# Mainboard.net
KiCad netlist of a schematic drawn in Altium Designer
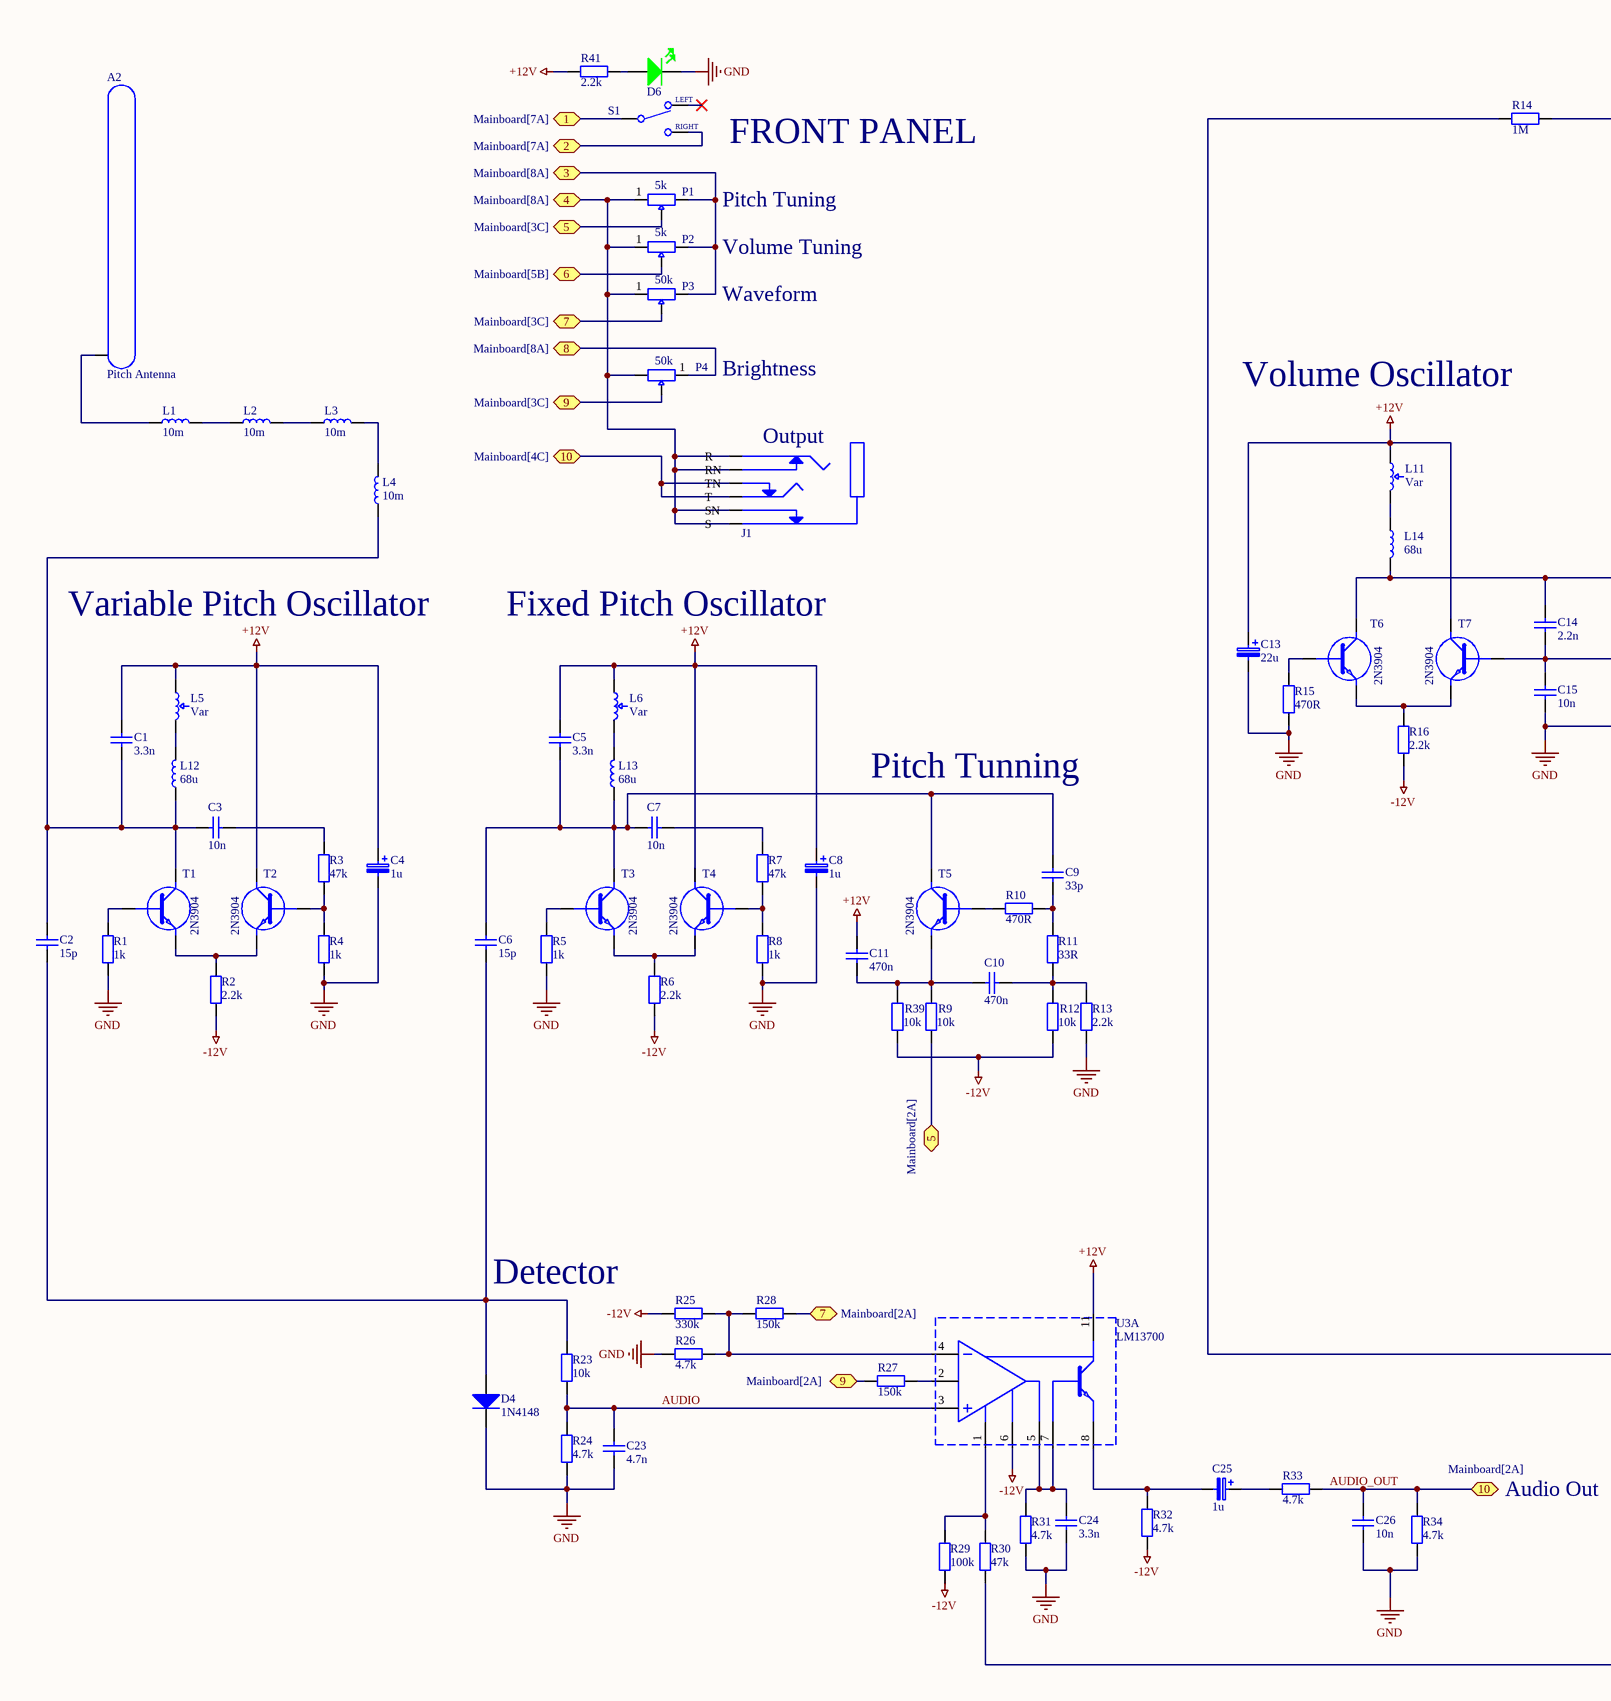
[diagram p0: Mainboard.SchDoc, left]
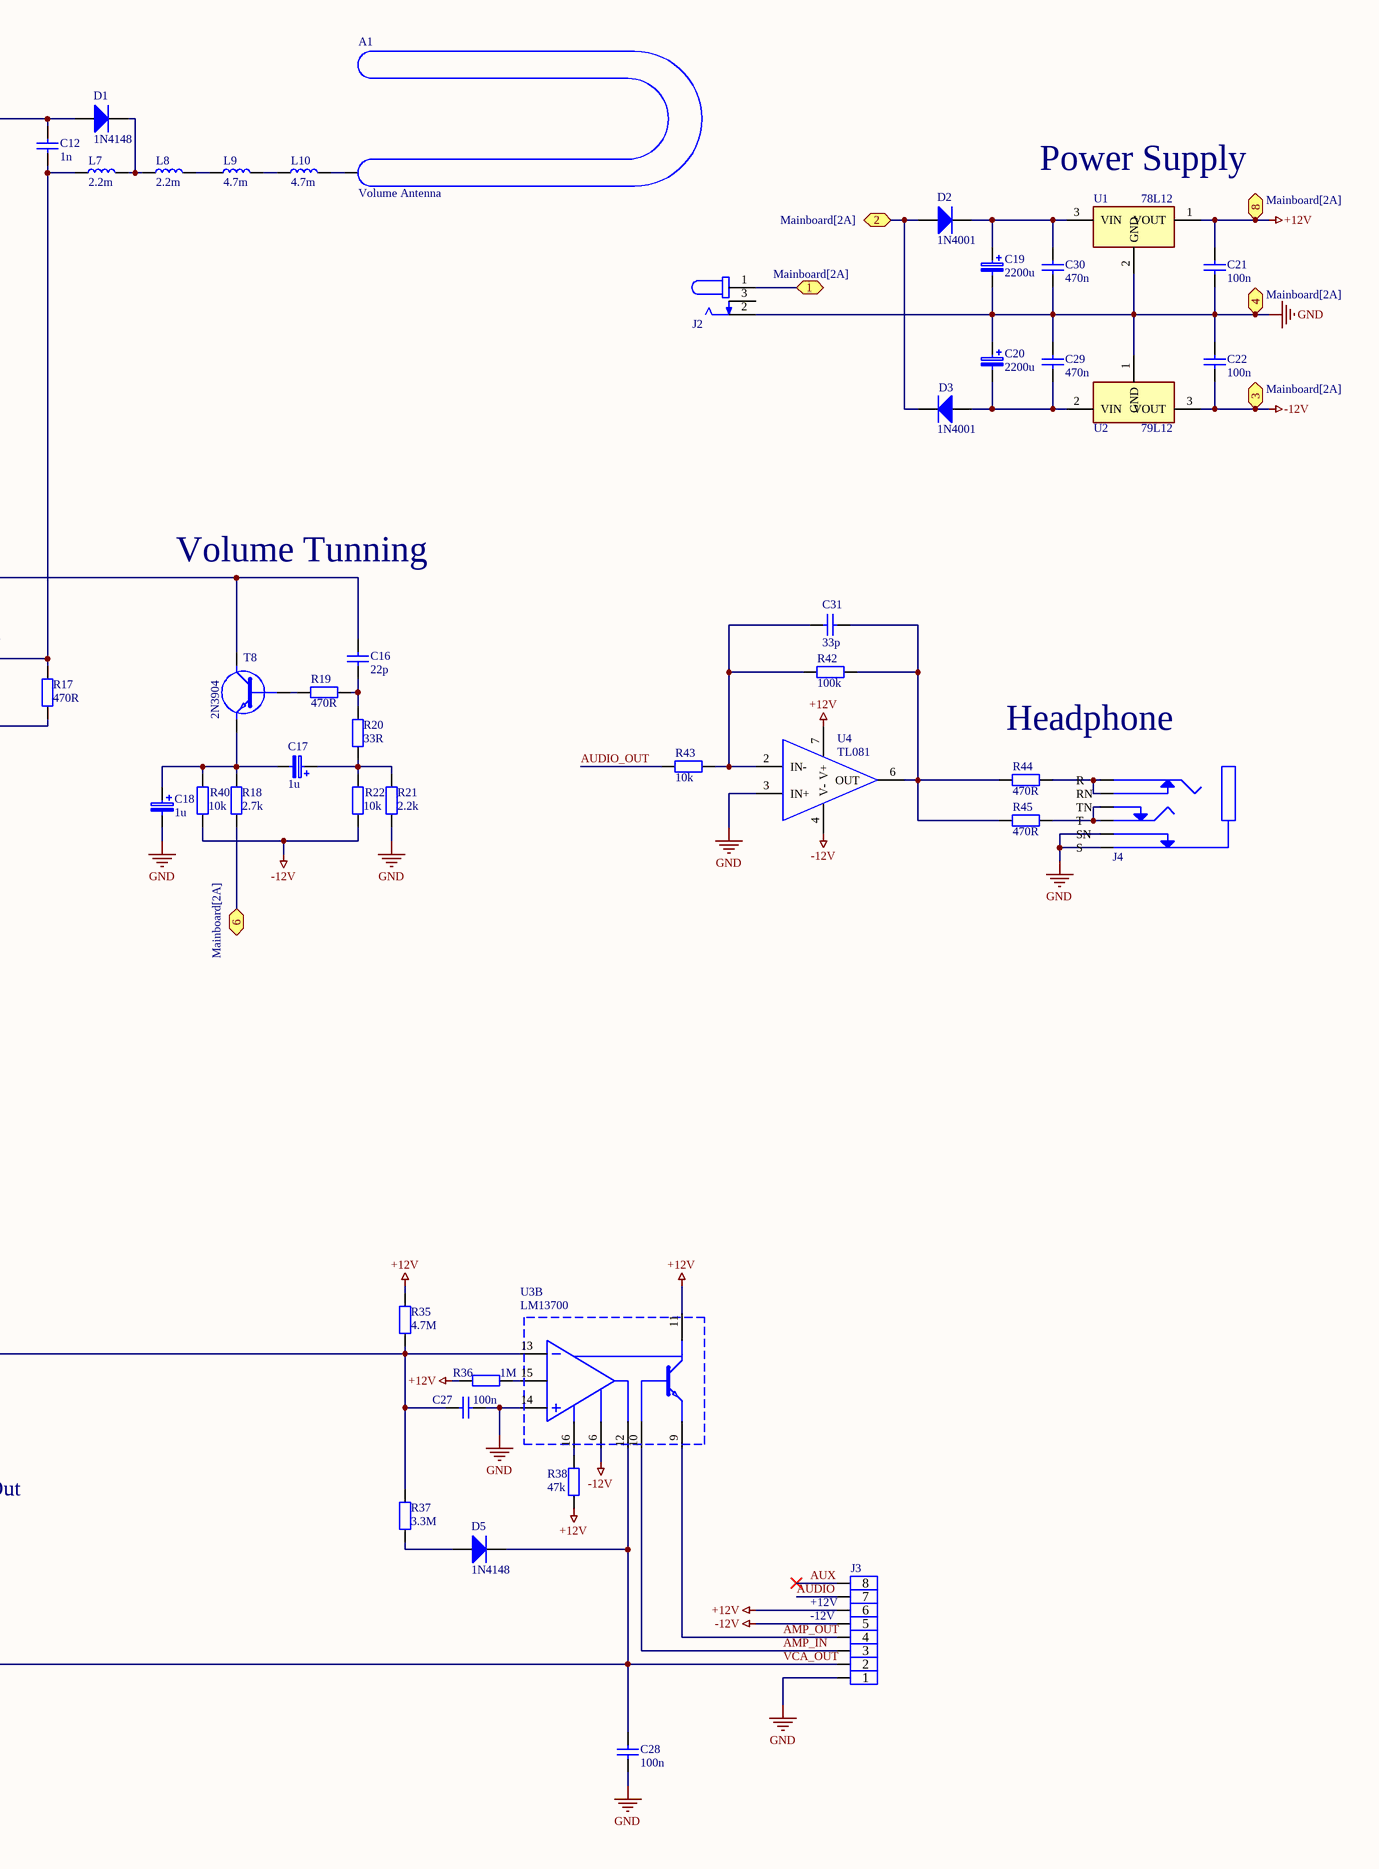
[diagram p1: Mainboard.SchDoc, right]

(export (version "E")
  (design (tool "Eeschema 10.0.6"))
  (components
    (comp (ref "A1")
      (value "Volume Antenna")
      (footprint "Theremin:HOLE M3")
      (libsource (lib "Theremin") (part "Mechanical Screw Antenna Volume M3"))
    )
    (comp (ref "A2")
      (value "Pitch Antenna")
      (footprint "Theremin:HOLE M3")
      (libsource (lib "Theremin") (part "Mechanical Screw Antenna Pitch M3"))
    )
    (comp (ref "C1")
      (value "3.3n")
      (footprint "Capacitor 7.2x3.5x6.5mm")
      (description "Capacitor: polyester; 3.3nF; 63VAC; 100VDC; 5mm; ±5%; 7.2x2.5x6.5mm")
      (fields (field (name "MPN") "R82EC1330DQ50J"))
      (libsource (lib "Theremin") (part "Capacitor 3.3n 63VAC 5mm 5% MKT THT"))
    )
    (comp (ref "C2")
      (value "15p")
      (footprint "Capacitor Ceramic")
      (description "Capacitor: ceramic; 15pF; 50V; C0G (NP0); ±5%; THT; 5mm")
      (fields (field (name "MPN") "RDE5C1H150J0M1H03A"))
      (libsource (lib "Theremin") (part "Capacitor 15p 50VAC 5mm 5% C0G THT"))
    )
    (comp (ref "C3")
      (value "10n")
      (footprint "Capacitor 7.2x3.5x6.5mm")
      (description "Capacitor: polyester; 0.01uF; 63VAC; 100VDC; 5mm; ±10%; -55÷125°C")
      (fields (field (name "MPN") "B32529C1103K289"))
      (libsource (lib "Theremin") (part "Capacitor 10n 63VAC 5mm 10% MKT THT"))
    )
    (comp (ref "C4")
      (value "1u")
      (footprint "Theremin:Capacitor Tantalum 5.08mm")
      (description "Capacitor: tantalum; 1uF; 35VDC; THT; ±20%; -55÷85°C; 2.54mm")
      (fields (field (name "MPN") "TC-1/35"))
      (libsource (lib "Theremin") (part "Capacitor 1u 35VAC 2.54mm 10% Tantalum THT"))
    )
    (comp (ref "C5")
      (value "3.3n")
      (footprint "Capacitor 7.2x3.5x6.5mm")
      (description "Capacitor: polyester; 3.3nF; 63VAC; 100VDC; 5mm; ±5%; 7.2x2.5x6.5mm")
      (fields (field (name "MPN") "R82EC1330DQ50J"))
      (libsource (lib "Theremin") (part "Capacitor 3.3n 63VAC 5mm 5% MKT THT"))
    )
    (comp (ref "C6")
      (value "15p")
      (footprint "Capacitor Ceramic")
      (description "Capacitor: ceramic; 15pF; 50V; C0G (NP0); ±5%; THT; 5mm")
      (fields (field (name "MPN") "RDE5C1H150J0M1H03A"))
      (libsource (lib "Theremin") (part "Capacitor 15p 50VAC 5mm 5% C0G THT"))
    )
    (comp (ref "C7")
      (value "10n")
      (footprint "Capacitor 7.2x3.5x6.5mm")
      (description "Capacitor: polyester; 0.01uF; 63VAC; 100VDC; 5mm; ±10%; -55÷125°C")
      (fields (field (name "MPN") "B32529C1103K289"))
      (libsource (lib "Theremin") (part "Capacitor 10n 63VAC 5mm 10% MKT THT"))
    )
    (comp (ref "C8")
      (value "1u")
      (footprint "Theremin:Capacitor Tantalum 5.08mm")
      (description "Capacitor: tantalum; 1uF; 35VDC; THT; ±20%; -55÷85°C; 2.54mm")
      (fields (field (name "MPN") "TC-1/35"))
      (libsource (lib "Theremin") (part "Capacitor 1u 35VAC 2.54mm 10% Tantalum THT"))
    )
    (comp (ref "C9")
      (value "33p")
      (footprint "Theremin:Capacitor Ceramic")
      (description "Capacitor: ceramic; 33pF; 50V; C0G (NP0); ±5%; THT; 5mm")
      (fields (field (name "MPN") "CT40805N330J500F3R"))
      (libsource (lib "Theremin") (part "Capacitor 33p 50VAC 5mm 5% C0G THT"))
    )
    (comp (ref "C10")
      (value "470n")
      (footprint "Theremin:Capacitor 7.2x3.5x6.5mm")
      (description "Capacitor: polyester; 470nF; 40VAC; 63VDC; 5mm; ±10%; 7.2x3.5x6.5mm")
      (fields (field (name "MPN") "R82DC3470DQ60K"))
      (libsource (lib "Theremin") (part "Capacitor 470n 63VAC 5mm 10% MKT THT"))
    )
    (comp (ref "C11")
      (value "470n")
      (footprint "Theremin:Capacitor 7.2x3.5x6.5mm")
      (description "Capacitor: polyester; 470nF; 40VAC; 63VDC; 5mm; ±10%; 7.2x3.5x6.5mm")
      (fields (field (name "MPN") "R82DC3470DQ60K"))
      (libsource (lib "Theremin") (part "Capacitor 470n 63VAC 5mm 10% MKT THT"))
    )
    (comp (ref "C12")
      (value "1n")
      (footprint "Capacitor 7.2x3.5x6.5mm")
      (description "Capacitor: polyester; 1nF; 63VAC; 100VDC; 5mm; ±10%; 7.2x2.5x6.5mm")
      (fields (field (name "MPN") "R82EC1100DQ50K"))
      (libsource (lib "Theremin") (part "Capacitor 1n 100VAC 5mm 10% MKT THT"))
    )
    (comp (ref "C13")
      (value "22u")
      (footprint "Theremin:Capacitor Tantalum 5.08mm")
      (description "Capacitor: tantalum; 22uF; 35VDC; THT; ±20%; -55÷85°C; 5.08mm")
      (fields (field (name "MPN") "TC-22/35"))
      (libsource (lib "Theremin") (part "Capacitor 22u 35VAC 2.54mm 20% Tantalum THT"))
    )
    (comp (ref "C14")
      (value "2.2n")
      (footprint "Capacitor 7.2x3.5x6.5mm")
      (description "Capacitor: polyester; 2.2nF; 63VAC; 100VDC; 5mm; ±10%; -55÷105°C")
      (fields (field (name "MPN") "R82EC1220DQ50K"))
      (libsource (lib "Theremin") (part "Capacitor 2.2n 63VAC 5mm 10% MKT THT"))
    )
    (comp (ref "C15")
      (value "10n")
      (footprint "Capacitor 7.2x3.5x6.5mm")
      (description "Capacitor: polyester; 0.01uF; 63VAC; 100VDC; 5mm; ±10%; -55÷125°C")
      (fields (field (name "MPN") "B32529C1103K289"))
      (libsource (lib "Theremin") (part "Capacitor 10n 63VAC 5mm 10% MKT THT"))
    )
    (comp (ref "C16")
      (value "22p")
      (footprint "Capacitor Ceramic")
      (description "Capacitor: ceramic; 22pF; 50V; C0G (NP0); ±5%; THT; 5mm")
      (fields (field (name "MPN") "CT40805N220J500F3R"))
      (libsource (lib "Theremin") (part "Capacitor 22p 50VAC 5mm 5% C0G THT"))
    )
    (comp (ref "C17")
      (value "1u")
      (footprint "Theremin:Capacitor Tantalum 5.08mm")
      (description "Capacitor: tantalum; 1uF; 35VDC; THT; ±20%; -55÷85°C; 2.54mm")
      (fields (field (name "MPN") "TC-1/35"))
      (libsource (lib "") (part "Capacitor 1u 35VAC 2.54mm 10% Tantalum THT_1"))
    )
    (comp (ref "C18")
      (value "1u")
      (footprint "Theremin:Capacitor Tantalum 5.08mm")
      (description "Capacitor: tantalum; 1uF; 35VDC; THT; ±20%; -55÷85°C; 2.54mm")
      (fields (field (name "MPN") "TC-1/35"))
      (libsource (lib "Theremin") (part "Capacitor 1u 35VAC 2.54mm 10% Tantalum THT"))
    )
    (comp (ref "C19")
      (value "2200u")
      (footprint "Theremin:Capacitor Electrolytic 16x25mm")
      (description "Capacitor: electrolytic; THT; 2200uF; 35VDC; Ø16x25mm; Pitch: 7.5mm")
      (fields (field (name "MPN") "EWH1VM222L25OT"))
      (libsource (lib "Theremin") (part "Capacitor 2200u 35VDC 7.5mm 20% Electrolytic THT"))
    )
    (comp (ref "C20")
      (value "2200u")
      (footprint "Theremin:Capacitor Electrolytic 16x25mm")
      (description "Capacitor: electrolytic; THT; 2200uF; 35VDC; Ø16x25mm; Pitch: 7.5mm")
      (fields (field (name "MPN") "EWH1VM222L25OT"))
      (libsource (lib "Theremin") (part "Capacitor 2200u 35VDC 7.5mm 20% Electrolytic THT"))
    )
    (comp (ref "C21")
      (value "100n")
      (footprint "Capacitor 7.2x3.5x6.5mm")
      (description "Capacitor: polyester; 100nF; 63VAC; 100VDC; 5mm; ±10%; -55÷100°C")
      (fields (field (name "MPN") "MKS2D031001A00KSSD"))
      (libsource (lib "Theremin") (part "Capacitor 100n 63VAC 5mm 10% MKT THT"))
    )
    (comp (ref "C22")
      (value "100n")
      (footprint "Capacitor 7.2x3.5x6.5mm")
      (description "Capacitor: polyester; 100nF; 63VAC; 100VDC; 5mm; ±10%; -55÷100°C")
      (fields (field (name "MPN") "MKS2D031001A00KSSD"))
      (libsource (lib "Theremin") (part "Capacitor 100n 63VAC 5mm 10% MKT THT"))
    )
    (comp (ref "C23")
      (value "4.7n")
      (footprint "Capacitor 7.2x3.5x6.5mm")
      (description "Capacitor: polyester; 4.7nF; 63VAC; 100VDC; 5mm; ±10%; -55÷105°C")
      (fields (field (name "MPN") "R82EC1470DQ50K"))
      (libsource (lib "Theremin") (part "Capacitor 4.7n 63VAC 5mm 5% MKT THT"))
    )
    (comp (ref "C24")
      (value "3.3n")
      (footprint "Capacitor 7.2x3.5x6.5mm")
      (description "Capacitor: polyester; 3.3nF; 63VAC; 100VDC; 5mm; ±5%; 7.2x2.5x6.5mm")
      (fields (field (name "MPN") "R82EC1330DQ50J"))
      (libsource (lib "Theremin") (part "Capacitor 3.3n 63VAC 5mm 5% MKT THT"))
    )
    (comp (ref "C25")
      (value "1u")
      (footprint "Theremin:Capacitor Tantalum 5.08mm")
      (description "Capacitor: tantalum; 1uF; 35VDC; THT; ±20%; -55÷85°C; 2.54mm")
      (fields (field (name "MPN") "TC-1/35"))
      (libsource (lib "Theremin") (part "Capacitor 1u 35VAC 2.54mm 10% Tantalum THT"))
    )
    (comp (ref "C26")
      (value "10n")
      (footprint "Capacitor 7.2x3.5x6.5mm")
      (description "Capacitor: polyester; 0.01uF; 63VAC; 100VDC; 5mm; ±10%; -55÷125°C")
      (fields (field (name "MPN") "B32529C1103K289"))
      (libsource (lib "Theremin") (part "Capacitor 10n 63VAC 5mm 10% MKT THT"))
    )
    (comp (ref "C27")
      (value "100n")
      (footprint "Capacitor 7.2x3.5x6.5mm")
      (description "Capacitor: polyester; 100nF; 63VAC; 100VDC; 5mm; ±10%; -55÷100°C")
      (fields (field (name "MPN") "MKS2D031001A00KSSD"))
      (libsource (lib "Theremin") (part "Capacitor 100n 63VAC 5mm 10% MKT THT"))
    )
    (comp (ref "C28")
      (value "100n")
      (footprint "Capacitor 7.2x3.5x6.5mm")
      (description "Capacitor: polyester; 100nF; 63VAC; 100VDC; 5mm; ±10%; -55÷100°C")
      (fields (field (name "MPN") "MKS2D031001A00KSSD"))
      (libsource (lib "Theremin") (part "Capacitor 100n 63VAC 5mm 10% MKT THT"))
    )
    (comp (ref "C29")
      (value "470n")
      (footprint "Theremin:Capacitor 7.2x3.5x6.5mm")
      (description "Capacitor: polyester; 470nF; 40VAC; 63VDC; 5mm; ±10%; 7.2x3.5x6.5mm")
      (fields (field (name "MPN") "R82DC3470DQ60K"))
      (libsource (lib "Theremin") (part "Capacitor 470n 63VAC 5mm 10% MKT THT"))
    )
    (comp (ref "C30")
      (value "470n")
      (footprint "Theremin:Capacitor 7.2x3.5x6.5mm")
      (description "Capacitor: polyester; 470nF; 40VAC; 63VDC; 5mm; ±10%; 7.2x3.5x6.5mm")
      (fields (field (name "MPN") "R82DC3470DQ60K"))
      (libsource (lib "Theremin") (part "Capacitor 470n 63VAC 5mm 10% MKT THT"))
    )
    (comp (ref "C31")
      (value "33p")
      (footprint "Theremin:Capacitor Ceramic")
      (description "Capacitor: ceramic; 33pF; 50V; C0G (NP0); ±5%; THT; 5mm")
      (fields (field (name "MPN") "CT40805N330J500F3R"))
      (libsource (lib "Theremin") (part "Capacitor 33p 50VAC 5mm 5% C0G THT"))
    )
    (comp (ref "D1")
      (value "1N4148")
      (footprint "DO35")
      (description "Diode: switching; THT; 100V; 0.2A; Ammo Pack; Ifsm: 4A; DO35; 500mW")
      (libsource (lib "Theremin") (part "Diode Signal DO35 1N4148 THT"))
    )
    (comp (ref "D2")
      (value "1N4001")
      (footprint "Theremin:DO41")
      (description "Diode: rectifying; THT; 50V; 1A; Ammo Pack; Ifsm: 30A; DO41")
      (libsource (lib "Theremin") (part "Diode Power DO41 1N4001 THT"))
    )
    (comp (ref "D3")
      (value "1N4001")
      (footprint "Theremin:DO41")
      (description "Diode: rectifying; THT; 50V; 1A; Ammo Pack; Ifsm: 30A; DO41")
      (libsource (lib "Theremin") (part "Diode Power DO41 1N4001 THT"))
    )
    (comp (ref "D4")
      (value "1N4148")
      (footprint "DO35")
      (description "Diode: switching; THT; 100V; 0.2A; Ammo Pack; Ifsm: 4A; DO35; 500mW")
      (libsource (lib "Theremin") (part "Diode Signal DO35 1N4148 THT"))
    )
    (comp (ref "D5")
      (value "1N4148")
      (footprint "DO35")
      (description "Diode: switching; THT; 100V; 0.2A; Ammo Pack; Ifsm: 4A; DO35; 500mW")
      (libsource (lib "Theremin") (part "Diode Signal DO35 1N4148 THT"))
    )
    (comp (ref "D6")
      (value "Green")
      (footprint "Theremin:LED 5mm")
      (description "LED; 5mm; green; 150÷350mcd; 45°; 1.9÷2.4V; No.of term: 2; -40÷85°C")
      (fields (field (name "MPN") "N0G02L47"))
      (libsource (lib "Theremin") (part "Diode LED 5mm THT Green Diffused"))
    )
    (comp (ref "J1")
      (value "JC-211")
      (footprint "Theremin:Jack 6.3mm PCB")
      (description "Socket; Jack 6,3mm; female; mono; ways: 2; for panel mounting; THT")
      (libsource (lib "Theremin") (part "Mechanical Jack 6.3mm Mono"))
    )
    (comp (ref "J2")
      (value "PC-GK2.1")
      (footprint "Theremin:DC Supply THT")
      (description "Socket; DC supply; male; 5.5/2.1mm; 5.5mm; 2.1mm; THT; angled 90°")
      (libsource (lib "Theremin") (part "Mechanical DC Conector 5.5/2.1mm THT"))
    )
    (comp (ref "J3")
      (value "8 PIN")
      (footprint "Theremin:Goldpin 8P")
      (description "Pin header; pin strips; male; PIN: 8; straight; 2.54mm; THT; 1x8")
      (fields (field (name "MPN") "DS1021-1*8SF11-B"))
      (libsource (lib "Theremin") (part "Mechanical Pinheader Male 8pin P=2.54mm THT"))
    )
    (comp (ref "J4")
      (value "JC-211")
      (footprint "Theremin:Jack 6.3mm PCB")
      (description "Socket; Jack 6,3mm; female; mono; ways: 2; for panel mounting; THT")
      (libsource (lib "Theremin") (part "Mechanical Jack 6.3mm Mono"))
    )
    (comp (ref "L1")
      (value "10m")
      (footprint "Theremin:Inductor 11.5x11.5")
      (description "Inductor: wire; THT; 10mH; Ioper: 250mA; 14.6Ω; ±10%; Ø11.5x11.5mm")
      (fields (field (name "MPN") "COIL1010-10"))
      (libsource (lib "Theremin") (part "Inductor Axial 10mH 250mA THT"))
    )
    (comp (ref "L2")
      (value "10m")
      (footprint "Theremin:Inductor 11.5x11.5")
      (description "Inductor: wire; THT; 10mH; Ioper: 250mA; 14.6Ω; ±10%; Ø11.5x11.5mm")
      (fields (field (name "MPN") "COIL1010-10"))
      (libsource (lib "Theremin") (part "Inductor Axial 10mH 250mA THT"))
    )
    (comp (ref "L3")
      (value "10m")
      (footprint "Theremin:Inductor 11.5x11.5")
      (description "Inductor: wire; THT; 10mH; Ioper: 250mA; 14.6Ω; ±10%; Ø11.5x11.5mm")
      (fields (field (name "MPN") "COIL1010-10"))
      (libsource (lib "") (part "Inductor Axial 10mH 250mA THT_1"))
    )
    (comp (ref "L4")
      (value "10m")
      (footprint "Theremin:Inductor 11.5x11.5")
      (description "Inductor: wire; THT; 10mH; Ioper: 250mA; 14.6Ω; ±10%; Ø11.5x11.5mm")
      (fields (field (name "MPN") "COIL1010-10"))
      (libsource (lib "Theremin") (part "Inductor Axial 10mH 250mA THT"))
    )
    (comp (ref "L5")
      (value "Var")
      (footprint "Theremin:Inductor Variable")
      (description "10pcs 50T 13uh-34uH Adjustable High-Frequency Ferrite Core Inductor Adjustable Tools")
      (fields (field (name "MPN") "50T 13uh-34uH"))
      (libsource (lib "Theremin") (part "Inductor Variable 13-34uH THT"))
    )
    (comp (ref "L6")
      (value "Var")
      (footprint "Theremin:Inductor Variable")
      (description "10pcs 50T 13uh-34uH Adjustable High-Frequency Ferrite Core Inductor Adjustable Tools")
      (fields (field (name "MPN") "50T 13uh-34uH"))
      (libsource (lib "Theremin") (part "Inductor Variable 13-34uH THT"))
    )
    (comp (ref "L7")
      (value "2.2m")
      (footprint "Theremin:Inductor 11.5x11.5")
      (description "Inductor: wire; THT; 2.2mH; Ioper: 550mA; 3.5Ω; ±10%; Ø11.5x11.5mm")
      (fields (field (name "MPN") "COIL1010-2.2"))
      (libsource (lib "Theremin") (part "Inductor Axial 2.2mH 550mA THT"))
    )
    (comp (ref "L8")
      (value "2.2m")
      (footprint "Theremin:Inductor 11.5x11.5")
      (description "Inductor: wire; THT; 2.2mH; Ioper: 550mA; 3.5Ω; ±10%; Ø11.5x11.5mm")
      (fields (field (name "MPN") "COIL1010-2.2"))
      (libsource (lib "Theremin") (part "Inductor Axial 2.2mH 550mA THT"))
    )
    (comp (ref "L9")
      (value "4.7m")
      (footprint "Theremin:Inductor 11.5x11.5")
      (description "Inductor: wire; THT; 4.7mH; Ioper: 400mA; 6Ω; ±10%; Ø11.5x11.5mm")
      (fields (field (name "MPN") "COIL1010-4.7"))
      (libsource (lib "Theremin") (part "Inductor Axial 4.7mH 400mA THT"))
    )
    (comp (ref "L10")
      (value "4.7m")
      (footprint "Theremin:Inductor 11.5x11.5")
      (description "Inductor: wire; THT; 4.7mH; Ioper: 400mA; 6Ω; ±10%; Ø11.5x11.5mm")
      (fields (field (name "MPN") "COIL1010-4.7"))
      (libsource (lib "Theremin") (part "Inductor Axial 4.7mH 400mA THT"))
    )
    (comp (ref "L11")
      (value "Var")
      (footprint "Theremin:Inductor Variable")
      (description "10pcs 50T 13uh-34uH Adjustable High-Frequency Ferrite Core Inductor Adjustable Tools")
      (fields (field (name "MPN") "50T 13uh-34uH"))
      (libsource (lib "Theremin") (part "Inductor Variable 13-34uH THT"))
    )
    (comp (ref "L12")
      (value "68u")
      (footprint "Theremin:Inductor Axial")
      (description "Inductor: axial; THT; 68uH; 185mA; 3.2Ω; Ø3x8mm")
      (fields (field (name "MPN") "DLA68-N"))
      (libsource (lib "Theremin") (part "Inductor Axial 68uH 185mA THT"))
    )
    (comp (ref "L13")
      (value "68u")
      (footprint "Theremin:Inductor Axial")
      (description "Inductor: axial; THT; 68uH; 185mA; 3.2Ω; Ø3x8mm")
      (fields (field (name "MPN") "DLA68-N"))
      (libsource (lib "Theremin") (part "Inductor Axial 68uH 185mA THT"))
    )
    (comp (ref "L14")
      (value "68u")
      (footprint "Theremin:Inductor Axial")
      (description "Inductor: axial; THT; 47uH; 205mA; 2.3Ω; Ø3x8mm")
      (fields (field (name "MPN") "DLA47-N"))
      (libsource (lib "Theremin") (part "Inductor Axial 47uH 205mA THT"))
    )
    (comp (ref "P1")
      (value "5k")
      (footprint "Theremin:Potentiometer Shaft")
      (description "Potentiometer: shaft; single turn; 5kΩ; 125mW; ±20%; THT; 6mm; metal")
      (fields (field (name "MPN") "R16148D-1A-2-B5K"))
      (libsource (lib "Theremin") (part "Potentiometer 5k 1/4W 5% THT"))
    )
    (comp (ref "P2")
      (value "5k")
      (footprint "Theremin:Potentiometer Shaft")
      (description "Potentiometer: shaft; single turn; 5kΩ; 125mW; ±20%; THT; 6mm; metal")
      (fields (field (name "MPN") "R16148D-1A-2-B5K"))
      (libsource (lib "Theremin") (part "Potentiometer 5k 1/4W 5% THT"))
    )
    (comp (ref "P3")
      (value "50k")
      (footprint "Theremin:Potentiometer Shaft")
      (description "Potentiometer: shaft; single turn; 50kΩ; 125mW; ±20%; THT; 6mm; mono")
      (fields (field (name "MPN") "R16148D-1A-2-B50K"))
      (libsource (lib "") (part "Potentiometer 50k 1/4W 5% THT_1"))
    )
    (comp (ref "P4")
      (value "50k")
      (footprint "Theremin:Potentiometer Shaft")
      (description "Potentiometer: shaft; single turn; 50kΩ; 125mW; ±20%; THT; 6mm; mono")
      (fields (field (name "MPN") "R16148D-1A-2-B50K"))
      (libsource (lib "Theremin") (part "Potentiometer 50k 1/4W 5% THT"))
    )
    (comp (ref "R1")
      (value "1k")
      (footprint "Resistor 1/4W")
      (description "Resistor: carbon film; THT; 1kΩ; 0.25W; ±5%; Ø2.3x6mm; axial")
      (fields (field (name "MPN") "CF1/4W-1K"))
      (libsource (lib "Theremin") (part "Resistor 1k 1/4W 5% THT"))
    )
    (comp (ref "R2")
      (value "2.2k")
      (footprint "Resistor 1/4W")
      (description "Resistor: carbon film; THT; 2.2kΩ; 0.25W; ±5%; Ø2.3x6mm; axial")
      (fields (field (name "MPN") "CF1/4W-2K2"))
      (libsource (lib "Theremin") (part "Resistor 2.2k 1/4W 5% THT"))
    )
    (comp (ref "R3")
      (value "47k")
      (footprint "Resistor 1/4W")
      (description "Resistor: carbon film; THT; 47kΩ; 0.25W; ±5%; Ø2.3x6mm; axial")
      (fields (field (name "MPN") "CF1/4W-47K"))
      (libsource (lib "Theremin") (part "Resistor 47k 1/4W 5% THT"))
    )
    (comp (ref "R4")
      (value "1k")
      (footprint "Resistor 1/4W")
      (description "Resistor: carbon film; THT; 1kΩ; 0.25W; ±5%; Ø2.3x6mm; axial")
      (fields (field (name "MPN") "CF1/4W-1K"))
      (libsource (lib "Theremin") (part "Resistor 1k 1/4W 5% THT"))
    )
    (comp (ref "R5")
      (value "1k")
      (footprint "Resistor 1/4W")
      (description "Resistor: carbon film; THT; 1kΩ; 0.25W; ±5%; Ø2.3x6mm; axial")
      (fields (field (name "MPN") "CF1/4W-1K"))
      (libsource (lib "Theremin") (part "Resistor 1k 1/4W 5% THT"))
    )
    (comp (ref "R6")
      (value "2.2k")
      (footprint "Resistor 1/4W")
      (description "Resistor: carbon film; THT; 2.2kΩ; 0.25W; ±5%; Ø2.3x6mm; axial")
      (fields (field (name "MPN") "CF1/4W-2K2"))
      (libsource (lib "Theremin") (part "Resistor 2.2k 1/4W 5% THT"))
    )
    (comp (ref "R7")
      (value "47k")
      (footprint "Resistor 1/4W")
      (description "Resistor: carbon film; THT; 47kΩ; 0.25W; ±5%; Ø2.3x6mm; axial")
      (fields (field (name "MPN") "CF1/4W-47K"))
      (libsource (lib "Theremin") (part "Resistor 47k 1/4W 5% THT"))
    )
    (comp (ref "R8")
      (value "1k")
      (footprint "Resistor 1/4W")
      (description "Resistor: carbon film; THT; 1kΩ; 0.25W; ±5%; Ø2.3x6mm; axial")
      (fields (field (name "MPN") "CF1/4W-1K"))
      (libsource (lib "Theremin") (part "Resistor 1k 1/4W 5% THT"))
    )
    (comp (ref "R9")
      (value "10k")
      (footprint "Resistor 1/4W")
      (description "Resistor: carbon film; THT; 10kΩ; 0.25W; ±5%; Ø2.3x6mm; axial")
      (fields (field (name "MPN") "CF1/4W-10K"))
      (libsource (lib "Theremin") (part "Resistor 10k 1/4W 5% THT"))
    )
    (comp (ref "R10")
      (value "470R")
      (footprint "Theremin:Resistor 1/4W")
      (description "Resistor: carbon film; THT; 470Ω; 0.25W; ±5%; Ø2.3x6mm; axial")
      (fields (field (name "MPN") "CF1/4W-470R"))
      (libsource (lib "Theremin") (part "Resistor 470R 1/4W 5% THT"))
    )
    (comp (ref "R11")
      (value "33R")
      (footprint "Resistor 1/4W")
      (description "Resistor: carbon film; THT; 33Ω; 0.25W; ±5%; Ø2.3x6mm; axial")
      (fields (field (name "MPN") "CF1/4W-33R"))
      (libsource (lib "Theremin") (part "Resistor 33R 1/4W 5% THT"))
    )
    (comp (ref "R12")
      (value "10k")
      (footprint "Resistor 1/4W")
      (description "Resistor: carbon film; THT; 10kΩ; 0.25W; ±5%; Ø2.3x6mm; axial")
      (fields (field (name "MPN") "CF1/4W-10K"))
      (libsource (lib "Theremin") (part "Resistor 10k 1/4W 5% THT"))
    )
    (comp (ref "R13")
      (value "2.2k")
      (footprint "Resistor 1/4W")
      (description "Resistor: carbon film; THT; 2.2kΩ; 0.25W; ±5%; Ø2.3x6mm; axial")
      (fields (field (name "MPN") "CF1/4W-2K2"))
      (libsource (lib "Theremin") (part "Resistor 2.2k 1/4W 5% THT"))
    )
    (comp (ref "R14")
      (value "1M")
      (footprint "Resistor 1/4W")
      (description "Resistor: carbon film; THT; 1MΩ; 0.25W; ±5%; Ø2.3x6mm; axial")
      (fields (field (name "MPN") "CF1/4W-1M"))
      (libsource (lib "") (part "Resistor 1M 1/4W 5% THT_1"))
    )
    (comp (ref "R15")
      (value "470R")
      (footprint "Theremin:Resistor 1/4W")
      (description "Resistor: carbon film; THT; 470Ω; 0.25W; ±5%; Ø2.3x6mm; axial")
      (fields (field (name "MPN") "CF1/4W-470R"))
      (libsource (lib "") (part "Resistor 470R 1/4W 5% THT_1"))
    )
    (comp (ref "R16")
      (value "2.2k")
      (footprint "Resistor 1/4W")
      (description "Resistor: carbon film; THT; 2.2kΩ; 0.25W; ±5%; Ø2.3x6mm; axial")
      (fields (field (name "MPN") "CF1/4W-2K2"))
      (libsource (lib "Theremin") (part "Resistor 2.2k 1/4W 5% THT"))
    )
    (comp (ref "R17")
      (value "470R")
      (footprint "Theremin:Resistor 1/4W")
      (description "Resistor: carbon film; THT; 470Ω; 0.25W; ±5%; Ø2.3x6mm; axial")
      (fields (field (name "MPN") "CF1/4W-470R"))
      (libsource (lib "") (part "Resistor 470R 1/4W 5% THT_1"))
    )
    (comp (ref "R18")
      (value "2.7k")
      (footprint "Resistor 1/4W")
      (description "Resistor: carbon film; THT; 2.7kΩ; 0.25W; ±5%; Ø2.3x6mm; axial")
      (fields (field (name "MPN") "CF1/4W-2K7"))
      (libsource (lib "Theremin") (part "Resistor 2.7k 1/4W 5% THT"))
    )
    (comp (ref "R19")
      (value "470R")
      (footprint "Theremin:Resistor 1/4W")
      (description "Resistor: carbon film; THT; 470Ω; 0.25W; ±5%; Ø2.3x6mm; axial")
      (fields (field (name "MPN") "CF1/4W-470R"))
      (libsource (lib "Theremin") (part "Resistor 470R 1/4W 5% THT"))
    )
    (comp (ref "R20")
      (value "33R")
      (footprint "Resistor 1/4W")
      (description "Resistor: carbon film; THT; 33Ω; 0.25W; ±5%; Ø2.3x6mm; axial")
      (fields (field (name "MPN") "CF1/4W-33R"))
      (libsource (lib "Theremin") (part "Resistor 33R 1/4W 5% THT"))
    )
    (comp (ref "R21")
      (value "2.2k")
      (footprint "Resistor 1/4W")
      (description "Resistor: carbon film; THT; 2.2kΩ; 0.25W; ±5%; Ø2.3x6mm; axial")
      (fields (field (name "MPN") "CF1/4W-2K2"))
      (libsource (lib "Theremin") (part "Resistor 2.2k 1/4W 5% THT"))
    )
    (comp (ref "R22")
      (value "10k")
      (footprint "Resistor 1/4W")
      (description "Resistor: carbon film; THT; 10kΩ; 0.25W; ±5%; Ø2.3x6mm; axial")
      (fields (field (name "MPN") "CF1/4W-10K"))
      (libsource (lib "Theremin") (part "Resistor 10k 1/4W 5% THT"))
    )
    (comp (ref "R23")
      (value "10k")
      (footprint "Resistor 1/4W")
      (description "Resistor: carbon film; THT; 10kΩ; 0.25W; ±5%; Ø2.3x6mm; axial")
      (fields (field (name "MPN") "CF1/4W-10K"))
      (libsource (lib "") (part "Resistor 10k 1/4W 5% THT_2"))
    )
    (comp (ref "R24")
      (value "4.7k")
      (footprint "Resistor 1/4W")
      (description "Resistor: carbon film; THT; 4.7kΩ; 0.25W; ±5%; Ø2.3x6mm; axial")
      (fields (field (name "MPN") "CF1/4W-4K7"))
      (libsource (lib "") (part "Resistor 4.7k 1/4W 5% THT_1"))
    )
    (comp (ref "R25")
      (value "330k")
      (footprint "Resistor 1/4W")
      (description "Resistor: carbon film; THT; 330kΩ; 0.25W; ±5%; Ø2.3x6mm; axial")
      (fields (field (name "MPN") "CF1/4W-330K"))
      (libsource (lib "Theremin") (part "Resistor 330k 1/4W 5% THT"))
    )
    (comp (ref "R26")
      (value "4.7k")
      (footprint "Resistor 1/4W")
      (description "Resistor: carbon film; THT; 4.7kΩ; 0.25W; ±5%; Ø2.3x6mm; axial")
      (fields (field (name "MPN") "CF1/4W-4K7"))
      (libsource (lib "") (part "Resistor 4.7k 1/4W 5% THT_3"))
    )
    (comp (ref "R27")
      (value "150k")
      (footprint "Resistor 1/4W")
      (description "Resistor: carbon film; THT; 150kΩ; 0.25W; ±5%; Ø2.3x6mm; axial")
      (fields (field (name "MPN") "CF1/4W-150K"))
      (libsource (lib "Theremin") (part "Resistor 150k 1/4W 5% THT"))
    )
    (comp (ref "R28")
      (value "150k")
      (footprint "Resistor 1/4W")
      (description "Resistor: carbon film; THT; 150kΩ; 0.25W; ±5%; Ø2.3x6mm; axial")
      (fields (field (name "MPN") "CF1/4W-150K"))
      (libsource (lib "") (part "Resistor 150k 1/4W 5% THT_1"))
    )
    (comp (ref "R29")
      (value "100k")
      (footprint "Resistor 1/4W")
      (description "Resistor: carbon film; THT; 100kΩ; 0.25W; ±5%; Ø2.3x6mm; axial")
      (fields (field (name "MPN") "CF1/4W-100K"))
      (libsource (lib "Theremin") (part "Resistor 100k 1/4W 5% THT"))
    )
    (comp (ref "R30")
      (value "47k")
      (footprint "Resistor 1/4W")
      (description "Resistor: carbon film; THT; 47kΩ; 0.25W; ±5%; Ø2.3x6mm; axial")
      (fields (field (name "MPN") "CF1/4W-47K"))
      (libsource (lib "Theremin") (part "Resistor 47k 1/4W 5% THT"))
    )
    (comp (ref "R31")
      (value "4.7k")
      (footprint "Resistor 1/4W")
      (description "Resistor: carbon film; THT; 4.7kΩ; 0.25W; ±5%; Ø2.3x6mm; axial")
      (fields (field (name "MPN") "CF1/4W-4K7"))
      (libsource (lib "") (part "Resistor 4.7k 1/4W 5% THT_1"))
    )
    (comp (ref "R32")
      (value "4.7k")
      (footprint "Resistor 1/4W")
      (description "Resistor: carbon film; THT; 4.7kΩ; 0.25W; ±5%; Ø2.3x6mm; axial")
      (fields (field (name "MPN") "CF1/4W-4K7"))
      (libsource (lib "") (part "Resistor 4.7k 1/4W 5% THT_1"))
    )
    (comp (ref "R33")
      (value "4.7k")
      (footprint "Resistor 1/4W")
      (description "Resistor: carbon film; THT; 4.7kΩ; 0.25W; ±5%; Ø2.3x6mm; axial")
      (fields (field (name "MPN") "CF1/4W-4K7"))
      (libsource (lib "Theremin") (part "Resistor 4.7k 1/4W 5% THT"))
    )
    (comp (ref "R34")
      (value "4.7k")
      (footprint "Resistor 1/4W")
      (description "Resistor: carbon film; THT; 4.7kΩ; 0.25W; ±5%; Ø2.3x6mm; axial")
      (fields (field (name "MPN") "CF1/4W-4K7"))
      (libsource (lib "") (part "Resistor 4.7k 1/4W 5% THT_2"))
    )
    (comp (ref "R35")
      (value "4.7M")
      (footprint "Resistor 1/4W")
      (description "Resistor: carbon film; THT; 4.7MΩ; 0.25W; ±5%; Ø2.3x6mm; axial")
      (fields (field (name "MPN") "CF1/4W-4M7"))
      (libsource (lib "Theremin") (part "Resistor 4.7M 1/4W 5% THT"))
    )
    (comp (ref "R36")
      (value "1M")
      (footprint "Resistor 1/4W")
      (description "Resistor: carbon film; THT; 1MΩ; 0.25W; ±5%; Ø2.3x6mm; axial")
      (fields (field (name "MPN") "CF1/4W-1M"))
      (libsource (lib "Theremin") (part "Resistor 1M 1/4W 5% THT"))
    )
    (comp (ref "R37")
      (value "3.3M")
      (footprint "Resistor 1/4W")
      (description "Resistor: carbon film; THT; 3.3MΩ; 0.25W; ±5%; Ø2.3x6mm; axial")
      (fields (field (name "MPN") "CF1/4W-3M3"))
      (libsource (lib "Theremin") (part "Resistor 3.3M 1/4W 5% THT"))
    )
    (comp (ref "R38")
      (value "47k")
      (footprint "Resistor 1/4W")
      (description "Resistor: carbon film; THT; 47kΩ; 0.25W; ±5%; Ø2.3x6mm; axial")
      (fields (field (name "MPN") "CF1/4W-47K"))
      (libsource (lib "Theremin") (part "Resistor 47k 1/4W 5% THT"))
    )
    (comp (ref "R39")
      (value "10k")
      (footprint "Resistor 1/4W")
      (description "Resistor: carbon film; THT; 10kΩ; 0.25W; ±5%; Ø2.3x6mm; axial")
      (fields (field (name "MPN") "CF1/4W-10K"))
      (libsource (lib "Theremin") (part "Resistor 10k 1/4W 5% THT"))
    )
    (comp (ref "R40")
      (value "10k")
      (footprint "Resistor 1/4W")
      (description "Resistor: carbon film; THT; 10kΩ; 0.25W; ±5%; Ø2.3x6mm; axial")
      (fields (field (name "MPN") "CF1/4W-10K"))
      (libsource (lib "Theremin") (part "Resistor 10k 1/4W 5% THT"))
    )
    (comp (ref "R41")
      (value "2.2k")
      (footprint "Resistor 1/4W")
      (description "Resistor: carbon film; THT; 2.2kΩ; 0.25W; ±5%; Ø2.3x6mm; axial")
      (fields (field (name "MPN") "CF1/4W-2K2"))
      (libsource (lib "") (part "Resistor 2.2k 1/4W 5% THT_1"))
    )
    (comp (ref "R42")
      (value "100k")
      (footprint "Resistor 1/4W")
      (description "Resistor: carbon film; THT; 100kΩ; 0.25W; ±5%; Ø2.3x6mm; axial")
      (fields (field (name "MPN") "CF1/4W-100K"))
      (libsource (lib "") (part "Resistor 100k 1/4W 5% THT_1"))
    )
    (comp (ref "R43")
      (value "10k")
      (footprint "Resistor 1/4W")
      (description "Resistor: carbon film; THT; 10kΩ; 0.25W; ±5%; Ø2.3x6mm; axial")
      (fields (field (name "MPN") "CF1/4W-10K"))
      (libsource (lib "") (part "Resistor 10k 1/4W 5% THT_1"))
    )
    (comp (ref "R44")
      (value "470R")
      (footprint "Theremin:Resistor 1/4W")
      (description "Resistor: carbon film; THT; 470Ω; 0.25W; ±5%; Ø2.3x6mm; axial")
      (fields (field (name "MPN") "CF1/4W-470R"))
      (libsource (lib "Theremin") (part "Resistor 470R 1/4W 5% THT"))
    )
    (comp (ref "R45")
      (value "470R")
      (footprint "Theremin:Resistor 1/4W")
      (description "Resistor: carbon film; THT; 470Ω; 0.25W; ±5%; Ø2.3x6mm; axial")
      (fields (field (name "MPN") "CF1/4W-470R"))
      (libsource (lib "Theremin") (part "Resistor 470R 1/4W 5% THT"))
    )
    (comp (ref "S1")
      (value "ON-ON")
      (footprint "Theremin:Switch Angled")
      (description "Switch: toggle; Pos: 2; SPDT; ON-ON; 0.4A/28VDC; -30÷85°C; 20mΩ")
      (fields (field (name "MPN") "SKS06LP"))
      (libsource (lib "Theremin") (part "Mechanical Switch Angled SPDT THT"))
    )
    (comp (ref "T1")
      (value "2N3904")
      (footprint "Theremin:TO-92")
      (description "Transistor: NPN; bipolar; 40V; 0.2A; 625mW; TO92")
      (libsource (lib "Theremin") (part "Transistor NPN 2N3904 THT"))
    )
    (comp (ref "T2")
      (value "2N3904")
      (footprint "Theremin:TO-92")
      (description "Transistor: NPN; bipolar; 40V; 0.2A; 625mW; TO92")
      (libsource (lib "Theremin") (part "Transistor NPN 2N3904 THT"))
    )
    (comp (ref "T3")
      (value "2N3904")
      (footprint "Theremin:TO-92")
      (description "Transistor: NPN; bipolar; 40V; 0.2A; 625mW; TO92")
      (libsource (lib "Theremin") (part "Transistor NPN 2N3904 THT"))
    )
    (comp (ref "T4")
      (value "2N3904")
      (footprint "Theremin:TO-92")
      (description "Transistor: NPN; bipolar; 40V; 0.2A; 625mW; TO92")
      (libsource (lib "Theremin") (part "Transistor NPN 2N3904 THT"))
    )
    (comp (ref "T5")
      (value "2N3904")
      (footprint "Theremin:TO-92")
      (description "Transistor: NPN; bipolar; 40V; 0.2A; 625mW; TO92")
      (libsource (lib "Theremin") (part "Transistor NPN 2N3904 THT"))
    )
    (comp (ref "T6")
      (value "2N3904")
      (footprint "Theremin:TO-92")
      (description "Transistor: NPN; bipolar; 40V; 0.2A; 625mW; TO92")
      (libsource (lib "Theremin") (part "Transistor NPN 2N3904 THT"))
    )
    (comp (ref "T7")
      (value "2N3904")
      (footprint "Theremin:TO-92")
      (description "Transistor: NPN; bipolar; 40V; 0.2A; 625mW; TO92")
      (libsource (lib "Theremin") (part "Transistor NPN 2N3904 THT"))
    )
    (comp (ref "T8")
      (value "2N3904")
      (footprint "Theremin:TO-92")
      (description "Transistor: NPN; bipolar; 40V; 0.2A; 625mW; TO92")
      (libsource (lib "Theremin") (part "Transistor NPN 2N3904 THT"))
    )
    (comp (ref "U1")
      (value "78L12")
      (footprint "Theremin:TO-92")
      (description "IC: voltage regulator; linear,fixed; 12V; 0.1A; TO92; THT; bulk")
      (fields (field (name "MPN") "MC78L12ACPG"))
      (libsource (lib "Theremin") (part "IC LDO 12V 0.1A TO92 THT"))
    )
    (comp (ref "U2")
      (value "79L12")
      (footprint "Theremin:TO-92")
      (description "IC: voltage regulator; linear,fixed; -12V; 0.1A; TO92; THT; bulk")
      (fields (field (name "MPN") "MC79L12ACPG"))
      (libsource (lib "Theremin") (part "IC LDO -12V 0.1A TO92 THT"))
    )
    (comp (ref "U3")
      (value "LM13700")
      (footprint "Theremin:SO-16")
      (description "IC: operational amplifier; 2MHz; Ch: 2; SO16;")
      (fields (field (name "MPN") "LM13700MX/NOPB"))
      (libsource (lib "Theremin") (part "IC OTA 2MHz SO16 SMD"))
    )
    (comp (ref "U4")
      (value "TL081")
      (footprint "Theremin:DIP-8")
      (description "IC: operational amplifier; 3MHz; Ch: 1; DIP8; ±5÷15VDC; tube")
      (fields (field (name "MPN") "TL081IP"))
      (libsource (lib "Theremin") (part "IC OP-AMP 3MHz TL081 DIP8"))
    )
  )
  (nets
    (net (code "1") (name "+12V") (class "Default")
      (node (ref "C1") (pin "2") (pinfunction "2_2") (pintype "passive"))
      (node (ref "C11") (pin "2") (pinfunction "2_2") (pintype "passive"))
      (node (ref "C13") (pin "1") (pinfunction "1_1") (pintype "passive"))
      (node (ref "C21") (pin "1") (pinfunction "1_1") (pintype "passive"))
      (node (ref "C4") (pin "1") (pinfunction "1_1") (pintype "passive"))
      (node (ref "C5") (pin "2") (pinfunction "2_2") (pintype "passive"))
      (node (ref "C8") (pin "1") (pinfunction "1_1") (pintype "passive"))
      (node (ref "J3") (pin "6") (pinfunction "6_6") (pintype "passive"))
      (node (ref "L11") (pin "2") (pinfunction "2_2") (pintype "passive"))
      (node (ref "L5") (pin "2") (pinfunction "2_2") (pintype "passive"))
      (node (ref "L6") (pin "2") (pinfunction "2_2") (pintype "passive"))
      (node (ref "P4") (pin "1") (pinfunction "1_1") (pintype "passive"))
      (node (ref "R35") (pin "2") (pinfunction "2_2") (pintype "passive"))
      (node (ref "R36") (pin "2") (pinfunction "2_2") (pintype "passive"))
      (node (ref "R38") (pin "1") (pinfunction "1_1") (pintype "passive"))
      (node (ref "R41") (pin "2") (pinfunction "2_2") (pintype "passive"))
      (node (ref "T2") (pin "3") (pinfunction "C_3") (pintype "passive"))
      (node (ref "T4") (pin "3") (pinfunction "C_3") (pintype "passive"))
      (node (ref "T7") (pin "3") (pinfunction "C_3") (pintype "passive"))
      (node (ref "U1") (pin "1") (pinfunction "VOUT_1") (pintype "passive"))
      (node (ref "U3") (pin "11") (pinfunction "V+_11") (pintype "passive"))
      (node (ref "U4") (pin "7") (pinfunction "V+_7") (pintype "passive"))
    )
    (net (code "2") (name "-12V") (class "Default")
      (node (ref "C22") (pin "2") (pinfunction "2_2") (pintype "passive"))
      (node (ref "J3") (pin "5") (pinfunction "5_5") (pintype "passive"))
      (node (ref "P1") (pin "3") (pinfunction "3_3") (pintype "passive"))
      (node (ref "P2") (pin "3") (pinfunction "3_3") (pintype "passive"))
      (node (ref "P3") (pin "3") (pinfunction "3_3") (pintype "passive"))
      (node (ref "R12") (pin "1") (pinfunction "1_1") (pintype "passive"))
      (node (ref "R16") (pin "1") (pinfunction "1_1") (pintype "passive"))
      (node (ref "R2") (pin "1") (pinfunction "1_1") (pintype "passive"))
      (node (ref "R22") (pin "1") (pinfunction "1_1") (pintype "passive"))
      (node (ref "R25") (pin "1") (pinfunction "1_1") (pintype "passive"))
      (node (ref "R29") (pin "1") (pinfunction "1_1") (pintype "passive"))
      (node (ref "R32") (pin "1") (pinfunction "1_1") (pintype "passive"))
      (node (ref "R39") (pin "1") (pinfunction "1_1") (pintype "passive"))
      (node (ref "R40") (pin "1") (pinfunction "1_1") (pintype "passive"))
      (node (ref "R6") (pin "1") (pinfunction "1_1") (pintype "passive"))
      (node (ref "U2") (pin "3") (pinfunction "VOUT_3") (pintype "passive"))
      (node (ref "U3") (pin "6") (pinfunction "V-_6") (pintype "passive"))
      (node (ref "U4") (pin "4") (pinfunction "V-_4") (pintype "passive"))
    )
    (net (code "3") (name "/1") (class "Default")
      (node (ref "J2") (pin "1") (pinfunction "1_1") (pintype "passive"))
      (node (ref "S1") (pin "2") (pinfunction "2_2") (pintype "passive"))
    )
    (net (code "4") (name "/2") (class "Default")
      (node (ref "D2") (pin "1") (pinfunction "1_1") (pintype "passive"))
      (node (ref "D3") (pin "2") (pinfunction "2_2") (pintype "passive"))
      (node (ref "S1") (pin "3") (pinfunction "3_3") (pintype "passive"))
    )
    (net (code "5") (name "/5") (class "Default")
      (node (ref "P1") (pin "2") (pinfunction "2_2") (pintype "passive"))
      (node (ref "R9") (pin "1") (pinfunction "1_1") (pintype "passive"))
    )
    (net (code "6") (name "/6") (class "Default")
      (node (ref "P2") (pin "2") (pinfunction "2_2") (pintype "passive"))
      (node (ref "R18") (pin "1") (pinfunction "1_1") (pintype "passive"))
    )
    (net (code "7") (name "/7") (class "Default")
      (node (ref "P3") (pin "2") (pinfunction "2_2") (pintype "passive"))
      (node (ref "R28") (pin "2") (pinfunction "2_2") (pintype "passive"))
    )
    (net (code "8") (name "/9") (class "Default")
      (node (ref "P4") (pin "2") (pinfunction "2_2") (pintype "passive"))
      (node (ref "R27") (pin "2") (pinfunction "2_2") (pintype "passive"))
    )
    (net (code "9") (name "/AMP_IN") (class "Default")
      (node (ref "J3") (pin "3") (pinfunction "3_3") (pintype "passive"))
      (node (ref "U3") (pin "10") (pinfunction "BUFFER_IN_10") (pintype "passive"))
    )
    (net (code "10") (name "/AMP_OUT") (class "Default")
      (node (ref "J3") (pin "4") (pinfunction "4_4") (pintype "passive"))
      (node (ref "U3") (pin "9") (pinfunction "BUFFER_OUT_9") (pintype "passive"))
    )
    (net (code "11") (name "/AUDIO") (class "Default")
      (node (ref "C23") (pin "2") (pinfunction "2_2") (pintype "passive"))
      (node (ref "J3") (pin "7") (pinfunction "7_7") (pintype "passive"))
      (node (ref "R23") (pin "2") (pinfunction "2_2") (pintype "passive"))
      (node (ref "R24") (pin "2") (pinfunction "2_2") (pintype "passive"))
      (node (ref "U3") (pin "3") (pinfunction "+_3") (pintype "passive"))
    )
    (net (code "12") (name "/AUDIO_OUT") (class "Default")
      (node (ref "C26") (pin "2") (pinfunction "2_2") (pintype "passive"))
      (node (ref "J1") (pin "3") (pinfunction "T_3") (pintype "passive"))
      (node (ref "J1") (pin "4") (pinfunction "TN_4") (pintype "passive"))
      (node (ref "R33") (pin "1") (pinfunction "1_1") (pintype "passive"))
      (node (ref "R34") (pin "1") (pinfunction "1_1") (pintype "passive"))
      (node (ref "R43") (pin "1") (pinfunction "1_1") (pintype "passive"))
    )
    (net (code "13") (name "/AUX") (class "Default")
      (node (ref "J3") (pin "8") (pinfunction "8_8") (pintype "passive+no_connect"))
    )
    (net (code "14") (name "/VCA_OUT") (class "Default")
      (node (ref "C28") (pin "2") (pinfunction "2_2") (pintype "passive"))
      (node (ref "D5") (pin "2") (pinfunction "2_2") (pintype "passive"))
      (node (ref "J3") (pin "2") (pinfunction "2_2") (pintype "passive"))
      (node (ref "R30") (pin "1") (pinfunction "1_1") (pintype "passive"))
      (node (ref "U3") (pin "12") (pinfunction "OUTPUT_12") (pintype "passive"))
    )
    (net (code "15") (name "GND") (class "Default")
      (node (ref "C13") (pin "2") (pinfunction "2_2") (pintype "passive"))
      (node (ref "C15") (pin "1") (pinfunction "1_1") (pintype "passive"))
      (node (ref "C18") (pin "2") (pinfunction "2_2") (pintype "passive"))
      (node (ref "C19") (pin "2") (pinfunction "2_2") (pintype "passive"))
      (node (ref "C20") (pin "1") (pinfunction "1_1") (pintype "passive"))
      (node (ref "C21") (pin "2") (pinfunction "2_2") (pintype "passive"))
      (node (ref "C22") (pin "1") (pinfunction "1_1") (pintype "passive"))
      (node (ref "C23") (pin "1") (pinfunction "1_1") (pintype "passive"))
      (node (ref "C24") (pin "1") (pinfunction "1_1") (pintype "passive"))
      (node (ref "C26") (pin "1") (pinfunction "1_1") (pintype "passive"))
      (node (ref "C27") (pin "1") (pinfunction "1_1") (pintype "passive"))
      (node (ref "C28") (pin "1") (pinfunction "1_1") (pintype "passive"))
      (node (ref "C29") (pin "2") (pinfunction "2_2") (pintype "passive"))
      (node (ref "C30") (pin "1") (pinfunction "1_1") (pintype "passive"))
      (node (ref "C4") (pin "2") (pinfunction "2_2") (pintype "passive"))
      (node (ref "C8") (pin "2") (pinfunction "2_2") (pintype "passive"))
      (node (ref "D4") (pin "2") (pinfunction "2_2") (pintype "passive"))
      (node (ref "D6") (pin "2") (pinfunction "2_2") (pintype "passive"))
      (node (ref "J1") (pin "1") (pinfunction "S_1") (pintype "passive"))
      (node (ref "J1") (pin "2") (pinfunction "R_2") (pintype "passive"))
      (node (ref "J1") (pin "5") (pinfunction "RN_5") (pintype "passive"))
      (node (ref "J1") (pin "6") (pinfunction "SN_6") (pintype "passive"))
      (node (ref "J2") (pin "2") (pinfunction "2_2") (pintype "passive"))
      (node (ref "J3") (pin "1") (pinfunction "1_1") (pintype "passive"))
      (node (ref "J4") (pin "1") (pinfunction "S_1") (pintype "passive"))
      (node (ref "J4") (pin "6") (pinfunction "SN_6") (pintype "passive"))
      (node (ref "P1") (pin "1") (pinfunction "1_1") (pintype "passive"))
      (node (ref "P2") (pin "1") (pinfunction "1_1") (pintype "passive"))
      (node (ref "P3") (pin "1") (pinfunction "1_1") (pintype "passive"))
      (node (ref "P4") (pin "3") (pinfunction "3_3") (pintype "passive"))
      (node (ref "R1") (pin "1") (pinfunction "1_1") (pintype "passive"))
      (node (ref "R13") (pin "1") (pinfunction "1_1") (pintype "passive"))
      (node (ref "R15") (pin "1") (pinfunction "1_1") (pintype "passive"))
      (node (ref "R17") (pin "1") (pinfunction "1_1") (pintype "passive"))
      (node (ref "R21") (pin "1") (pinfunction "1_1") (pintype "passive"))
      (node (ref "R24") (pin "1") (pinfunction "1_1") (pintype "passive"))
      (node (ref "R26") (pin "1") (pinfunction "1_1") (pintype "passive"))
      (node (ref "R31") (pin "1") (pinfunction "1_1") (pintype "passive"))
      (node (ref "R34") (pin "2") (pinfunction "2_2") (pintype "passive"))
      (node (ref "R4") (pin "1") (pinfunction "1_1") (pintype "passive"))
      (node (ref "R5") (pin "1") (pinfunction "1_1") (pintype "passive"))
      (node (ref "R8") (pin "1") (pinfunction "1_1") (pintype "passive"))
      (node (ref "U1") (pin "2") (pinfunction "GND_2") (pintype "passive"))
      (node (ref "U2") (pin "1") (pinfunction "GND_1") (pintype "passive"))
      (node (ref "U3") (pin "14") (pinfunction "+_14") (pintype "passive"))
      (node (ref "U4") (pin "3") (pinfunction "IN+_3") (pintype "passive"))
    )
    (net (code "16") (name "Net-(A1-Pad1)") (class "Default")
      (node (ref "A1") (pin "1") (pinfunction "1_1") (pintype "passive"))
      (node (ref "L10") (pin "2") (pinfunction "2_2") (pintype "passive"))
    )
    (net (code "17") (name "Net-(A2-Pad1)") (class "Default")
      (node (ref "A2") (pin "1") (pinfunction "1_1") (pintype "passive"))
      (node (ref "L1") (pin "1") (pinfunction "1_1") (pintype "passive"))
    )
    (net (code "18") (name "Net-(C2-Pad1)") (class "Default")
      (node (ref "C2") (pin "1") (pinfunction "1_1") (pintype "passive"))
      (node (ref "C6") (pin "1") (pinfunction "1_1") (pintype "passive"))
      (node (ref "D4") (pin "1") (pinfunction "1_1") (pintype "passive"))
      (node (ref "R23") (pin "1") (pinfunction "1_1") (pintype "passive"))
    )
    (net (code "19") (name "Net-(C3-Pad2)") (class "Default")
      (node (ref "C3") (pin "2") (pinfunction "2_2") (pintype "passive"))
      (node (ref "R3") (pin "2") (pinfunction "2_2") (pintype "passive"))
    )
    (net (code "20") (name "Net-(C7-Pad2)") (class "Default")
      (node (ref "C7") (pin "2") (pinfunction "2_2") (pintype "passive"))
      (node (ref "R7") (pin "2") (pinfunction "2_2") (pintype "passive"))
    )
    (net (code "21") (name "Net-(C9-Pad1)") (class "Default")
      (node (ref "C9") (pin "1") (pinfunction "1_1") (pintype "passive"))
      (node (ref "R10") (pin "2") (pinfunction "2_2") (pintype "passive"))
      (node (ref "R11") (pin "2") (pinfunction "2_2") (pintype "passive"))
    )
    (net (code "22") (name "Net-(C10-Pad1)") (class "Default")
      (node (ref "C10") (pin "1") (pinfunction "1_1") (pintype "passive"))
      (node (ref "R11") (pin "1") (pinfunction "1_1") (pintype "passive"))
      (node (ref "R12") (pin "2") (pinfunction "2_2") (pintype "passive"))
      (node (ref "R13") (pin "2") (pinfunction "2_2") (pintype "passive"))
    )
    (net (code "23") (name "Net-(C12-Pad2)") (class "Default")
      (node (ref "C12") (pin "2") (pinfunction "2_2") (pintype "passive"))
      (node (ref "D1") (pin "1") (pinfunction "1_1") (pintype "passive"))
      (node (ref "R14") (pin "2") (pinfunction "2_2") (pintype "passive"))
    )
    (net (code "24") (name "Net-(C16-Pad1)") (class "Default")
      (node (ref "C16") (pin "1") (pinfunction "1_1") (pintype "passive"))
      (node (ref "R19") (pin "2") (pinfunction "2_2") (pintype "passive"))
      (node (ref "R20") (pin "2") (pinfunction "2_2") (pintype "passive"))
    )
    (net (code "25") (name "Net-(C17-Pad1)") (class "Default")
      (node (ref "C17") (pin "1") (pinfunction "1_1") (pintype "passive"))
      (node (ref "R20") (pin "1") (pinfunction "1_1") (pintype "passive"))
      (node (ref "R21") (pin "2") (pinfunction "2_2") (pintype "passive"))
      (node (ref "R22") (pin "2") (pinfunction "2_2") (pintype "passive"))
    )
    (net (code "26") (name "Net-(C25-Pad1)") (class "Default")
      (node (ref "C25") (pin "1") (pinfunction "1_1") (pintype "passive"))
      (node (ref "R33") (pin "2") (pinfunction "2_2") (pintype "passive"))
    )
    (net (code "27") (name "Net-(D1-Pad2)") (class "Default")
      (node (ref "D1") (pin "2") (pinfunction "2_2") (pintype "passive"))
      (node (ref "L7") (pin "2") (pinfunction "2_2") (pintype "passive"))
      (node (ref "L8") (pin "1") (pinfunction "1_1") (pintype "passive"))
    )
    (net (code "28") (name "Net-(D5-Pad1)") (class "Default")
      (node (ref "D5") (pin "1") (pinfunction "1_1") (pintype "passive"))
      (node (ref "R37") (pin "1") (pinfunction "1_1") (pintype "passive"))
    )
    (net (code "29") (name "Net-(D6-Pad1)") (class "Default")
      (node (ref "D6") (pin "1") (pinfunction "1_1") (pintype "passive"))
      (node (ref "R41") (pin "1") (pinfunction "1_1") (pintype "passive"))
    )
    (net (code "30") (name "Net-(J4-R)") (class "Default")
      (node (ref "J4") (pin "2") (pinfunction "R_2") (pintype "passive"))
      (node (ref "J4") (pin "5") (pinfunction "RN_5") (pintype "passive"))
      (node (ref "R44") (pin "2") (pinfunction "2_2") (pintype "passive"))
    )
    (net (code "31") (name "Net-(J4-T)") (class "Default")
      (node (ref "J4") (pin "3") (pinfunction "T_3") (pintype "passive"))
      (node (ref "J4") (pin "4") (pinfunction "TN_4") (pintype "passive"))
      (node (ref "R45") (pin "2") (pinfunction "2_2") (pintype "passive"))
    )
    (net (code "32") (name "Net-(L1-Pad2)") (class "Default")
      (node (ref "L1") (pin "2") (pinfunction "2_2") (pintype "passive"))
      (node (ref "L2") (pin "1") (pinfunction "1_1") (pintype "passive"))
    )
    (net (code "33") (name "Net-(L2-Pad2)") (class "Default")
      (node (ref "L2") (pin "2") (pinfunction "2_2") (pintype "passive"))
      (node (ref "L3") (pin "2") (pinfunction "2_2") (pintype "passive"))
    )
    (net (code "34") (name "Net-(L3-Pad1)") (class "Default")
      (node (ref "L3") (pin "1") (pinfunction "1_1") (pintype "passive"))
      (node (ref "L4") (pin "2") (pinfunction "2_2") (pintype "passive"))
    )
    (net (code "35") (name "Net-(L8-Pad2)") (class "Default")
      (node (ref "L8") (pin "2") (pinfunction "2_2") (pintype "passive"))
      (node (ref "L9") (pin "1") (pinfunction "1_1") (pintype "passive"))
    )
    (net (code "36") (name "Net-(L10-Pad1)") (class "Default")
      (node (ref "L10") (pin "1") (pinfunction "1_1") (pintype "passive"))
      (node (ref "L9") (pin "2") (pinfunction "2_2") (pintype "passive"))
    )
    (net (code "37") (name "Net-(L11-Pad1)") (class "Default")
      (node (ref "L11") (pin "1") (pinfunction "1_1") (pintype "passive"))
      (node (ref "L14") (pin "1") (pinfunction "1_1") (pintype "passive"))
    )
    (net (code "38") (name "Net-(L12-Pad2)") (class "Default")
      (node (ref "L12") (pin "2") (pinfunction "2_2") (pintype "passive"))
      (node (ref "L5") (pin "1") (pinfunction "1_1") (pintype "passive"))
    )
    (net (code "39") (name "Net-(L13-Pad2)") (class "Default")
      (node (ref "L13") (pin "2") (pinfunction "2_2") (pintype "passive"))
      (node (ref "L6") (pin "1") (pinfunction "1_1") (pintype "passive"))
    )
    (net (code "40") (name "Net-(T1-B)") (class "Default")
      (node (ref "R1") (pin "2") (pinfunction "2_2") (pintype "passive"))
      (node (ref "T1") (pin "2") (pinfunction "B_2") (pintype "passive"))
    )
    (net (code "41") (name "Net-(T1-C)") (class "Default")
      (node (ref "C1") (pin "1") (pinfunction "1_1") (pintype "passive"))
      (node (ref "C2") (pin "2") (pinfunction "2_2") (pintype "passive"))
      (node (ref "C3") (pin "1") (pinfunction "1_1") (pintype "passive"))
      (node (ref "L12") (pin "1") (pinfunction "1_1") (pintype "passive"))
      (node (ref "L4") (pin "1") (pinfunction "1_1") (pintype "passive"))
      (node (ref "T1") (pin "3") (pinfunction "C_3") (pintype "passive"))
    )
    (net (code "42") (name "Net-(T1-E)") (class "Default")
      (node (ref "R2") (pin "2") (pinfunction "2_2") (pintype "passive"))
      (node (ref "T1") (pin "1") (pinfunction "E_1") (pintype "passive"))
      (node (ref "T2") (pin "1") (pinfunction "E_1") (pintype "passive"))
    )
    (net (code "43") (name "Net-(T2-B)") (class "Default")
      (node (ref "R3") (pin "1") (pinfunction "1_1") (pintype "passive"))
      (node (ref "R4") (pin "2") (pinfunction "2_2") (pintype "passive"))
      (node (ref "T2") (pin "2") (pinfunction "B_2") (pintype "passive"))
    )
    (net (code "44") (name "Net-(T3-B)") (class "Default")
      (node (ref "R5") (pin "2") (pinfunction "2_2") (pintype "passive"))
      (node (ref "T3") (pin "2") (pinfunction "B_2") (pintype "passive"))
    )
    (net (code "45") (name "Net-(T3-C)") (class "Default")
      (node (ref "C5") (pin "1") (pinfunction "1_1") (pintype "passive"))
      (node (ref "C6") (pin "2") (pinfunction "2_2") (pintype "passive"))
      (node (ref "C7") (pin "1") (pinfunction "1_1") (pintype "passive"))
      (node (ref "C9") (pin "2") (pinfunction "2_2") (pintype "passive"))
      (node (ref "L13") (pin "1") (pinfunction "1_1") (pintype "passive"))
      (node (ref "T3") (pin "3") (pinfunction "C_3") (pintype "passive"))
      (node (ref "T5") (pin "3") (pinfunction "C_3") (pintype "passive"))
    )
    (net (code "46") (name "Net-(T3-E)") (class "Default")
      (node (ref "R6") (pin "2") (pinfunction "2_2") (pintype "passive"))
      (node (ref "T3") (pin "1") (pinfunction "E_1") (pintype "passive"))
      (node (ref "T4") (pin "1") (pinfunction "E_1") (pintype "passive"))
    )
    (net (code "47") (name "Net-(T4-B)") (class "Default")
      (node (ref "R7") (pin "1") (pinfunction "1_1") (pintype "passive"))
      (node (ref "R8") (pin "2") (pinfunction "2_2") (pintype "passive"))
      (node (ref "T4") (pin "2") (pinfunction "B_2") (pintype "passive"))
    )
    (net (code "48") (name "Net-(T5-B)") (class "Default")
      (node (ref "R10") (pin "1") (pinfunction "1_1") (pintype "passive"))
      (node (ref "T5") (pin "2") (pinfunction "B_2") (pintype "passive"))
    )
    (net (code "49") (name "Net-(T5-E)") (class "Default")
      (node (ref "C10") (pin "2") (pinfunction "2_2") (pintype "passive"))
      (node (ref "C11") (pin "1") (pinfunction "1_1") (pintype "passive"))
      (node (ref "R39") (pin "2") (pinfunction "2_2") (pintype "passive"))
      (node (ref "R9") (pin "2") (pinfunction "2_2") (pintype "passive"))
      (node (ref "T5") (pin "1") (pinfunction "E_1") (pintype "passive"))
    )
    (net (code "50") (name "Net-(T6-B)") (class "Default")
      (node (ref "R15") (pin "2") (pinfunction "2_2") (pintype "passive"))
      (node (ref "T6") (pin "2") (pinfunction "B_2") (pintype "passive"))
    )
    (net (code "51") (name "Net-(T6-C)") (class "Default")
      (node (ref "C14") (pin "2") (pinfunction "2_2") (pintype "passive"))
      (node (ref "C16") (pin "2") (pinfunction "2_2") (pintype "passive"))
      (node (ref "L14") (pin "2") (pinfunction "2_2") (pintype "passive"))
      (node (ref "T6") (pin "3") (pinfunction "C_3") (pintype "passive"))
      (node (ref "T8") (pin "3") (pinfunction "C_3") (pintype "passive"))
    )
    (net (code "52") (name "Net-(T6-E)") (class "Default")
      (node (ref "R16") (pin "2") (pinfunction "2_2") (pintype "passive"))
      (node (ref "T6") (pin "1") (pinfunction "E_1") (pintype "passive"))
      (node (ref "T7") (pin "1") (pinfunction "E_1") (pintype "passive"))
    )
    (net (code "53") (name "Net-(T7-B)") (class "Default")
      (node (ref "C12") (pin "1") (pinfunction "1_1") (pintype "passive"))
      (node (ref "C14") (pin "1") (pinfunction "1_1") (pintype "passive"))
      (node (ref "C15") (pin "2") (pinfunction "2_2") (pintype "passive"))
      (node (ref "L7") (pin "1") (pinfunction "1_1") (pintype "passive"))
      (node (ref "R17") (pin "2") (pinfunction "2_2") (pintype "passive"))
      (node (ref "T7") (pin "2") (pinfunction "B_2") (pintype "passive"))
    )
    (net (code "54") (name "Net-(T8-B)") (class "Default")
      (node (ref "R19") (pin "1") (pinfunction "1_1") (pintype "passive"))
      (node (ref "T8") (pin "2") (pinfunction "B_2") (pintype "passive"))
    )
    (net (code "55") (name "Net-(T8-E)") (class "Default")
      (node (ref "C17") (pin "2") (pinfunction "2_2") (pintype "passive"))
      (node (ref "C18") (pin "1") (pinfunction "1_1") (pintype "passive"))
      (node (ref "R18") (pin "2") (pinfunction "2_2") (pintype "passive"))
      (node (ref "R40") (pin "2") (pinfunction "2_2") (pintype "passive"))
      (node (ref "T8") (pin "1") (pinfunction "E_1") (pintype "passive"))
    )
    (net (code "56") (name "Net-(U1-VIN)") (class "Default")
      (node (ref "C19") (pin "1") (pinfunction "1_1") (pintype "passive"))
      (node (ref "C30") (pin "2") (pinfunction "2_2") (pintype "passive"))
      (node (ref "D2") (pin "2") (pinfunction "2_2") (pintype "passive"))
      (node (ref "U1") (pin "3") (pinfunction "VIN_3") (pintype "passive"))
    )
    (net (code "57") (name "Net-(U2-VIN)") (class "Default")
      (node (ref "C20") (pin "2") (pinfunction "2_2") (pintype "passive"))
      (node (ref "C29") (pin "1") (pinfunction "1_1") (pintype "passive"))
      (node (ref "D3") (pin "1") (pinfunction "1_1") (pintype "passive"))
      (node (ref "U2") (pin "2") (pinfunction "VIN_2") (pintype "passive"))
    )
    (net (code "58") (name "Net-(U3A--)") (class "Default")
      (node (ref "R25") (pin "2") (pinfunction "2_2") (pintype "passive"))
      (node (ref "R26") (pin "2") (pinfunction "2_2") (pintype "passive"))
      (node (ref "R28") (pin "1") (pinfunction "1_1") (pintype "passive"))
      (node (ref "U3") (pin "4") (pinfunction "-_4") (pintype "passive"))
    )
    (net (code "59") (name "Net-(U3A-BIAS_AMP)") (class "Default")
      (node (ref "R29") (pin "2") (pinfunction "2_2") (pintype "passive"))
      (node (ref "R30") (pin "2") (pinfunction "2_2") (pintype "passive"))
      (node (ref "U3") (pin "1") (pinfunction "BIAS_AMP_1") (pintype "passive"))
    )
    (net (code "60") (name "Net-(U3A-BIAS_DIODE)") (class "Default")
      (node (ref "R27") (pin "1") (pinfunction "1_1") (pintype "passive"))
      (node (ref "U3") (pin "2") (pinfunction "BIAS_DIODE_2") (pintype "passive"))
    )
    (net (code "61") (name "Net-(U3A-BUFFER_IN)") (class "Default")
      (node (ref "C24") (pin "2") (pinfunction "2_2") (pintype "passive"))
      (node (ref "R31") (pin "2") (pinfunction "2_2") (pintype "passive"))
      (node (ref "U3") (pin "5") (pinfunction "OUTPUT_5") (pintype "passive"))
      (node (ref "U3") (pin "7") (pinfunction "BUFFER_IN_7") (pintype "passive"))
    )
    (net (code "62") (name "Net-(U3A-BUFFER_OUT)") (class "Default")
      (node (ref "C25") (pin "2") (pinfunction "2_2") (pintype "passive"))
      (node (ref "R32") (pin "2") (pinfunction "2_2") (pintype "passive"))
      (node (ref "U3") (pin "8") (pinfunction "BUFFER_OUT_8") (pintype "passive"))
    )
    (net (code "63") (name "Net-(U3B--)") (class "Default")
      (node (ref "C27") (pin "2") (pinfunction "2_2") (pintype "passive"))
      (node (ref "R14") (pin "1") (pinfunction "1_1") (pintype "passive"))
      (node (ref "R35") (pin "1") (pinfunction "1_1") (pintype "passive"))
      (node (ref "R37") (pin "2") (pinfunction "2_2") (pintype "passive"))
      (node (ref "U3") (pin "13") (pinfunction "-_13") (pintype "passive"))
    )
    (net (code "64") (name "Net-(U3B-BIAS_AMP)") (class "Default")
      (node (ref "R38") (pin "2") (pinfunction "2_2") (pintype "passive"))
      (node (ref "U3") (pin "16") (pinfunction "BIAS_AMP_16") (pintype "passive"))
    )
    (net (code "65") (name "Net-(U3B-BIAS_DIODE)") (class "Default")
      (node (ref "R36") (pin "1") (pinfunction "1_1") (pintype "passive"))
      (node (ref "U3") (pin "15") (pinfunction "BIAS_DIODE_15") (pintype "passive"))
    )
    (net (code "66") (name "Net-(U4-IN-)") (class "Default")
      (node (ref "C31") (pin "1") (pinfunction "1_1") (pintype "passive"))
      (node (ref "R42") (pin "1") (pinfunction "1_1") (pintype "passive"))
      (node (ref "R43") (pin "2") (pinfunction "2_2") (pintype "passive"))
      (node (ref "U4") (pin "2") (pinfunction "IN-_2") (pintype "passive"))
    )
    (net (code "67") (name "Net-(U4-OUT)") (class "Default")
      (node (ref "C31") (pin "2") (pinfunction "2_2") (pintype "passive"))
      (node (ref "R42") (pin "2") (pinfunction "2_2") (pintype "passive"))
      (node (ref "R44") (pin "1") (pinfunction "1_1") (pintype "passive"))
      (node (ref "R45") (pin "1") (pinfunction "1_1") (pintype "passive"))
      (node (ref "U4") (pin "6") (pinfunction "OUT_6") (pintype "passive"))
    )
    (net (code "68") (name "unconnected-(J2-Pad3)") (class "Default")
      (node (ref "J2") (pin "3") (pinfunction "3_3") (pintype "passive"))
    )
    (net (code "69") (name "unconnected-(S1-Pad1)") (class "Default")
      (node (ref "S1") (pin "1") (pinfunction "1_1") (pintype "passive+no_connect"))
    )
  )
)
